# Debug.net
KiCad netlist of a schematic drawn in Altium Designer
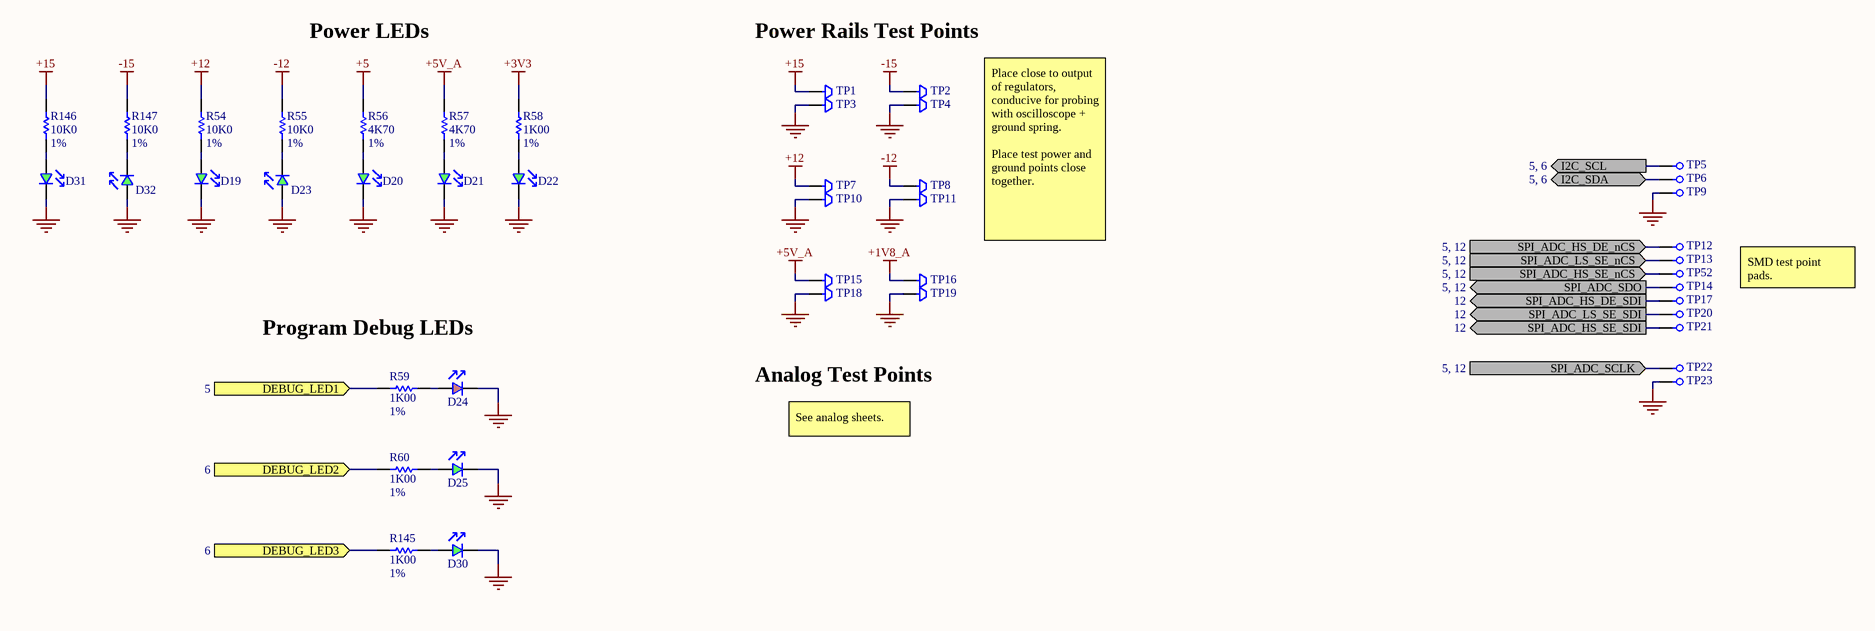
[diagram p0: Debug.SchDoc]

(export (version "E")
  (design (tool "Eeschema 10.0.6"))
  (components
    (comp (ref "D19")
      (value "LED Green")
      (footprint "0603 LED")
      (description "Generic Green LED")
      (libsource (lib "MRT SCH Library") (part "LED Green"))
    )
    (comp (ref "D20")
      (value "LED Green")
      (footprint "0603 LED")
      (description "Generic Green LED")
      (libsource (lib "MRT SCH Library") (part "LED Green"))
    )
    (comp (ref "D21")
      (value "LED Green")
      (footprint "0603 LED")
      (description "Generic Green LED")
      (libsource (lib "MRT SCH Library") (part "LED Green"))
    )
    (comp (ref "D22")
      (value "LED Green")
      (footprint "0603 LED")
      (description "Generic Green LED")
      (libsource (lib "MRT SCH Library") (part "LED Green"))
    )
    (comp (ref "D23")
      (value "LED Green")
      (footprint "0603 LED")
      (description "Generic Green LED")
      (libsource (lib "MRT SCH Library") (part "LED Green"))
    )
    (comp (ref "D24")
      (value "LED Red")
      (footprint "0603 LED")
      (description "Generic Red LED")
      (libsource (lib "MRT SCH Library") (part "LED Red"))
    )
    (comp (ref "D25")
      (value "LED Green")
      (footprint "0603 LED")
      (description "Generic Green LED")
      (libsource (lib "MRT SCH Library") (part "LED Green"))
    )
    (comp (ref "D30")
      (value "LED Green")
      (footprint "0603 LED")
      (description "Generic Green LED")
      (libsource (lib "MRT SCH Library") (part "LED Green"))
    )
    (comp (ref "D31")
      (value "LED Green")
      (footprint "0603 LED")
      (description "Generic Green LED")
      (libsource (lib "MRT SCH Library") (part "LED Green"))
    )
    (comp (ref "D32")
      (value "LED Green")
      (footprint "0603 LED")
      (description "Generic Green LED")
      (libsource (lib "MRT SCH Library") (part "LED Green"))
    )
    (comp (ref "R54")
      (value "10K0")
      (footprint "0402 RES")
      (description "Resistor")
      (fields (field (name "ALTIUM_VALUE") "1%") (field (name "PUBLISHER") "Altium Limited"))
      (libsource (lib "Miscellaneous Devices") (part "Res1"))
    )
    (comp (ref "R55")
      (value "10K0")
      (footprint "0402 RES")
      (description "Resistor")
      (fields (field (name "ALTIUM_VALUE") "1%") (field (name "PUBLISHER") "Altium Limited"))
      (libsource (lib "Miscellaneous Devices") (part "Res1"))
    )
    (comp (ref "R56")
      (value "4K70")
      (footprint "0402 RES")
      (description "Resistor")
      (fields (field (name "ALTIUM_VALUE") "1%") (field (name "PUBLISHER") "Altium Limited"))
      (libsource (lib "Miscellaneous Devices") (part "Res1"))
    )
    (comp (ref "R57")
      (value "4K70")
      (footprint "0402 RES")
      (description "Resistor")
      (fields (field (name "ALTIUM_VALUE") "1%") (field (name "PUBLISHER") "Altium Limited"))
      (libsource (lib "Miscellaneous Devices") (part "Res1"))
    )
    (comp (ref "R58")
      (value "1K00")
      (footprint "0402 RES")
      (description "Resistor")
      (fields (field (name "ALTIUM_VALUE") "1%") (field (name "PUBLISHER") "Altium Limited"))
      (libsource (lib "Miscellaneous Devices") (part "Res1"))
    )
    (comp (ref "R59")
      (value "1K00")
      (footprint "0402 RES")
      (description "Resistor")
      (fields (field (name "ALTIUM_VALUE") "1%") (field (name "PUBLISHER") "Altium Limited"))
      (libsource (lib "Miscellaneous Devices") (part "Res1"))
    )
    (comp (ref "R60")
      (value "1K00")
      (footprint "0402 RES")
      (description "Resistor")
      (fields (field (name "ALTIUM_VALUE") "1%") (field (name "PUBLISHER") "Altium Limited"))
      (libsource (lib "Miscellaneous Devices") (part "Res1"))
    )
    (comp (ref "R145")
      (value "1K00")
      (footprint "0402 RES")
      (description "Resistor")
      (fields (field (name "ALTIUM_VALUE") "1%") (field (name "PUBLISHER") "Altium Limited"))
      (libsource (lib "Miscellaneous Devices") (part "Res1"))
    )
    (comp (ref "R146")
      (value "10K0")
      (footprint "0402 RES")
      (description "Resistor")
      (fields (field (name "ALTIUM_VALUE") "1%") (field (name "PUBLISHER") "Altium Limited"))
      (libsource (lib "Miscellaneous Devices") (part "Res1"))
    )
    (comp (ref "R147")
      (value "10K0")
      (footprint "0402 RES")
      (description "Resistor")
      (fields (field (name "ALTIUM_VALUE") "1%") (field (name "PUBLISHER") "Altium Limited"))
      (libsource (lib "Miscellaneous Devices") (part "Res1"))
    )
    (comp (ref "TP1")
      (value "Test Point - Keystone 5015")
      (footprint "Test Point Keystone 5015")
      (description "Keystone 5015 Test point")
      (libsource (lib "MRT SCH Library") (part "Test Point - Keystone 5015"))
    )
    (comp (ref "TP2")
      (value "Test Point - Keystone 5015")
      (footprint "Test Point Keystone 5015")
      (description "Keystone 5015 Test point")
      (libsource (lib "MRT SCH Library") (part "Test Point - Keystone 5015"))
    )
    (comp (ref "TP3")
      (value "Test Point - Keystone 5015")
      (footprint "Test Point Keystone 5015")
      (description "Keystone 5015 Test point")
      (libsource (lib "MRT SCH Library") (part "Test Point - Keystone 5015"))
    )
    (comp (ref "TP4")
      (value "Test Point - Keystone 5015")
      (footprint "Test Point Keystone 5015")
      (description "Keystone 5015 Test point")
      (libsource (lib "MRT SCH Library") (part "Test Point - Keystone 5015"))
    )
    (comp (ref "TP5")
      (value "Test Point - SMD Pad")
      (footprint "TEST POINT SMD PAD")
      (description "SMD Pad test point")
      (libsource (lib "MRT SCH Library") (part "Test Point - SMD Pad"))
    )
    (comp (ref "TP6")
      (value "Test Point - SMD Pad")
      (footprint "TEST POINT SMD PAD")
      (description "SMD Pad test point")
      (libsource (lib "MRT SCH Library") (part "Test Point - SMD Pad"))
    )
    (comp (ref "TP7")
      (value "Test Point - Keystone 5015")
      (footprint "Test Point Keystone 5015")
      (description "Keystone 5015 Test point")
      (libsource (lib "MRT SCH Library") (part "Test Point - Keystone 5015"))
    )
    (comp (ref "TP8")
      (value "Test Point - Keystone 5015")
      (footprint "Test Point Keystone 5015")
      (description "Keystone 5015 Test point")
      (libsource (lib "MRT SCH Library") (part "Test Point - Keystone 5015"))
    )
    (comp (ref "TP9")
      (value "Test Point - SMD Pad")
      (footprint "TEST POINT SMD PAD")
      (description "SMD Pad test point")
      (libsource (lib "MRT SCH Library") (part "Test Point - SMD Pad"))
    )
    (comp (ref "TP10")
      (value "Test Point - Keystone 5015")
      (footprint "Test Point Keystone 5015")
      (description "Keystone 5015 Test point")
      (libsource (lib "MRT SCH Library") (part "Test Point - Keystone 5015"))
    )
    (comp (ref "TP11")
      (value "Test Point - Keystone 5015")
      (footprint "Test Point Keystone 5015")
      (description "Keystone 5015 Test point")
      (libsource (lib "MRT SCH Library") (part "Test Point - Keystone 5015"))
    )
    (comp (ref "TP12")
      (value "Test Point - SMD Pad")
      (footprint "TEST POINT SMD PAD")
      (description "SMD Pad test point")
      (libsource (lib "MRT SCH Library") (part "Test Point - SMD Pad"))
    )
    (comp (ref "TP13")
      (value "Test Point - SMD Pad")
      (footprint "TEST POINT SMD PAD")
      (description "SMD Pad test point")
      (libsource (lib "MRT SCH Library") (part "Test Point - SMD Pad"))
    )
    (comp (ref "TP14")
      (value "Test Point - SMD Pad")
      (footprint "TEST POINT SMD PAD")
      (description "SMD Pad test point")
      (libsource (lib "MRT SCH Library") (part "Test Point - SMD Pad"))
    )
    (comp (ref "TP15")
      (value "Test Point - Keystone 5015")
      (footprint "Test Point Keystone 5015")
      (description "Keystone 5015 Test point")
      (libsource (lib "MRT SCH Library") (part "Test Point - Keystone 5015"))
    )
    (comp (ref "TP16")
      (value "Test Point - Keystone 5015")
      (footprint "Test Point Keystone 5015")
      (description "Keystone 5015 Test point")
      (libsource (lib "MRT SCH Library") (part "Test Point - Keystone 5015"))
    )
    (comp (ref "TP17")
      (value "Test Point - SMD Pad")
      (footprint "TEST POINT SMD PAD")
      (description "SMD Pad test point")
      (libsource (lib "MRT SCH Library") (part "Test Point - SMD Pad"))
    )
    (comp (ref "TP18")
      (value "Test Point - Keystone 5015")
      (footprint "Test Point Keystone 5015")
      (description "Keystone 5015 Test point")
      (libsource (lib "MRT SCH Library") (part "Test Point - Keystone 5015"))
    )
    (comp (ref "TP19")
      (value "Test Point - Keystone 5015")
      (footprint "Test Point Keystone 5015")
      (description "Keystone 5015 Test point")
      (libsource (lib "MRT SCH Library") (part "Test Point - Keystone 5015"))
    )
    (comp (ref "TP20")
      (value "Test Point - SMD Pad")
      (footprint "TEST POINT SMD PAD")
      (description "SMD Pad test point")
      (libsource (lib "MRT SCH Library") (part "Test Point - SMD Pad"))
    )
    (comp (ref "TP21")
      (value "Test Point - SMD Pad")
      (footprint "TEST POINT SMD PAD")
      (description "SMD Pad test point")
      (libsource (lib "MRT SCH Library") (part "Test Point - SMD Pad"))
    )
    (comp (ref "TP22")
      (value "Test Point - SMD Pad")
      (footprint "TEST POINT SMD PAD")
      (description "SMD Pad test point")
      (libsource (lib "MRT SCH Library") (part "Test Point - SMD Pad"))
    )
    (comp (ref "TP23")
      (value "Test Point - SMD Pad")
      (footprint "TEST POINT SMD PAD")
      (description "SMD Pad test point")
      (libsource (lib "MRT SCH Library") (part "Test Point - SMD Pad"))
    )
    (comp (ref "TP52")
      (value "Test Point - SMD Pad")
      (footprint "TEST POINT SMD PAD")
      (description "SMD Pad test point")
      (libsource (lib "MRT SCH Library") (part "Test Point - SMD Pad"))
    )
  )
  (nets
    (net (code "1") (name "+1V8_A") (class "Default")
      (node (ref "TP16") (pin "1") (pinfunction "1_1") (pintype "passive"))
    )
    (net (code "2") (name "+3V3") (class "Default")
      (node (ref "R58") (pin "2") (pinfunction "2_2") (pintype "passive"))
    )
    (net (code "3") (name "+5") (class "Default")
      (node (ref "R56") (pin "2") (pinfunction "2_2") (pintype "passive"))
    )
    (net (code "4") (name "+5V_A") (class "Default")
      (node (ref "R57") (pin "2") (pinfunction "2_2") (pintype "passive"))
      (node (ref "TP15") (pin "1") (pinfunction "1_1") (pintype "passive"))
    )
    (net (code "5") (name "+12") (class "Default")
      (node (ref "R54") (pin "2") (pinfunction "2_2") (pintype "passive"))
      (node (ref "TP7") (pin "1") (pinfunction "1_1") (pintype "passive"))
    )
    (net (code "6") (name "+15") (class "Default")
      (node (ref "R146") (pin "2") (pinfunction "2_2") (pintype "passive"))
      (node (ref "TP1") (pin "1") (pinfunction "1_1") (pintype "passive"))
    )
    (net (code "7") (name "-12") (class "Default")
      (node (ref "R55") (pin "2") (pinfunction "2_2") (pintype "passive"))
      (node (ref "TP8") (pin "1") (pinfunction "1_1") (pintype "passive"))
    )
    (net (code "8") (name "-15") (class "Default")
      (node (ref "R147") (pin "2") (pinfunction "2_2") (pintype "passive"))
      (node (ref "TP2") (pin "1") (pinfunction "1_1") (pintype "passive"))
    )
    (net (code "9") (name "/DEBUG_LED1") (class "Default")
      (node (ref "R59") (pin "2") (pinfunction "2_2") (pintype "passive"))
    )
    (net (code "10") (name "/DEBUG_LED2") (class "Default")
      (node (ref "R60") (pin "2") (pinfunction "2_2") (pintype "passive"))
    )
    (net (code "11") (name "/DEBUG_LED3") (class "Default")
      (node (ref "R145") (pin "2") (pinfunction "2_2") (pintype "passive"))
    )
    (net (code "12") (name "/I2C_SCL") (class "Default")
      (node (ref "TP5") (pin "1") (pinfunction "1_1") (pintype "passive"))
    )
    (net (code "13") (name "/I2C_SDA") (class "Default")
      (node (ref "TP6") (pin "1") (pinfunction "1_1") (pintype "passive"))
    )
    (net (code "14") (name "/SPI_ADC_HS_DE_SDI") (class "Default")
      (node (ref "TP17") (pin "1") (pinfunction "1_1") (pintype "passive"))
    )
    (net (code "15") (name "/SPI_ADC_HS_DE_nCS") (class "Default")
      (node (ref "TP12") (pin "1") (pinfunction "1_1") (pintype "passive"))
    )
    (net (code "16") (name "/SPI_ADC_HS_SE_SDI") (class "Default")
      (node (ref "TP21") (pin "1") (pinfunction "1_1") (pintype "passive"))
    )
    (net (code "17") (name "/SPI_ADC_HS_SE_nCS") (class "Default")
      (node (ref "TP52") (pin "1") (pinfunction "1_1") (pintype "passive"))
    )
    (net (code "18") (name "/SPI_ADC_LS_SE_SDI") (class "Default")
      (node (ref "TP20") (pin "1") (pinfunction "1_1") (pintype "passive"))
    )
    (net (code "19") (name "/SPI_ADC_LS_SE_nCS") (class "Default")
      (node (ref "TP13") (pin "1") (pinfunction "1_1") (pintype "passive"))
    )
    (net (code "20") (name "/SPI_ADC_SCLK") (class "Default")
      (node (ref "TP22") (pin "1") (pinfunction "1_1") (pintype "passive"))
    )
    (net (code "21") (name "/SPI_ADC_SDO") (class "Default")
      (node (ref "TP14") (pin "1") (pinfunction "1_1") (pintype "passive"))
    )
    (net (code "22") (name "GND") (class "Default")
      (node (ref "D19") (pin "2") (pinfunction "Cathode_2") (pintype "passive"))
      (node (ref "D20") (pin "2") (pinfunction "Cathode_2") (pintype "passive"))
      (node (ref "D21") (pin "2") (pinfunction "Cathode_2") (pintype "passive"))
      (node (ref "D22") (pin "2") (pinfunction "Cathode_2") (pintype "passive"))
      (node (ref "D23") (pin "1") (pinfunction "Anode_1") (pintype "passive"))
      (node (ref "D24") (pin "2") (pinfunction "Cathode_2") (pintype "passive"))
      (node (ref "D25") (pin "2") (pinfunction "Cathode_2") (pintype "passive"))
      (node (ref "D30") (pin "2") (pinfunction "Cathode_2") (pintype "passive"))
      (node (ref "D31") (pin "2") (pinfunction "Cathode_2") (pintype "passive"))
      (node (ref "D32") (pin "1") (pinfunction "Anode_1") (pintype "passive"))
      (node (ref "TP10") (pin "1") (pinfunction "1_1") (pintype "passive"))
      (node (ref "TP11") (pin "1") (pinfunction "1_1") (pintype "passive"))
      (node (ref "TP18") (pin "1") (pinfunction "1_1") (pintype "passive"))
      (node (ref "TP19") (pin "1") (pinfunction "1_1") (pintype "passive"))
      (node (ref "TP23") (pin "1") (pinfunction "1_1") (pintype "passive"))
      (node (ref "TP3") (pin "1") (pinfunction "1_1") (pintype "passive"))
      (node (ref "TP4") (pin "1") (pinfunction "1_1") (pintype "passive"))
      (node (ref "TP9") (pin "1") (pinfunction "1_1") (pintype "passive"))
    )
    (net (code "23") (name "Net-(D19-Anode)") (class "Default")
      (node (ref "D19") (pin "1") (pinfunction "Anode_1") (pintype "passive"))
      (node (ref "R54") (pin "1") (pinfunction "1_1") (pintype "passive"))
    )
    (net (code "24") (name "Net-(D20-Anode)") (class "Default")
      (node (ref "D20") (pin "1") (pinfunction "Anode_1") (pintype "passive"))
      (node (ref "R56") (pin "1") (pinfunction "1_1") (pintype "passive"))
    )
    (net (code "25") (name "Net-(D21-Anode)") (class "Default")
      (node (ref "D21") (pin "1") (pinfunction "Anode_1") (pintype "passive"))
      (node (ref "R57") (pin "1") (pinfunction "1_1") (pintype "passive"))
    )
    (net (code "26") (name "Net-(D22-Anode)") (class "Default")
      (node (ref "D22") (pin "1") (pinfunction "Anode_1") (pintype "passive"))
      (node (ref "R58") (pin "1") (pinfunction "1_1") (pintype "passive"))
    )
    (net (code "27") (name "Net-(D23-Cathode)") (class "Default")
      (node (ref "D23") (pin "2") (pinfunction "Cathode_2") (pintype "passive"))
      (node (ref "R55") (pin "1") (pinfunction "1_1") (pintype "passive"))
    )
    (net (code "28") (name "Net-(D24-Anode)") (class "Default")
      (node (ref "D24") (pin "1") (pinfunction "Anode_1") (pintype "passive"))
      (node (ref "R59") (pin "1") (pinfunction "1_1") (pintype "passive"))
    )
    (net (code "29") (name "Net-(D25-Anode)") (class "Default")
      (node (ref "D25") (pin "1") (pinfunction "Anode_1") (pintype "passive"))
      (node (ref "R60") (pin "1") (pinfunction "1_1") (pintype "passive"))
    )
    (net (code "30") (name "Net-(D30-Anode)") (class "Default")
      (node (ref "D30") (pin "1") (pinfunction "Anode_1") (pintype "passive"))
      (node (ref "R145") (pin "1") (pinfunction "1_1") (pintype "passive"))
    )
    (net (code "31") (name "Net-(D31-Anode)") (class "Default")
      (node (ref "D31") (pin "1") (pinfunction "Anode_1") (pintype "passive"))
      (node (ref "R146") (pin "1") (pinfunction "1_1") (pintype "passive"))
    )
    (net (code "32") (name "Net-(D32-Cathode)") (class "Default")
      (node (ref "D32") (pin "2") (pinfunction "Cathode_2") (pintype "passive"))
      (node (ref "R147") (pin "1") (pinfunction "1_1") (pintype "passive"))
    )
  )
)
